# ai_firefly_prog.net
KiCad netlist of a schematic drawn in EAGLE
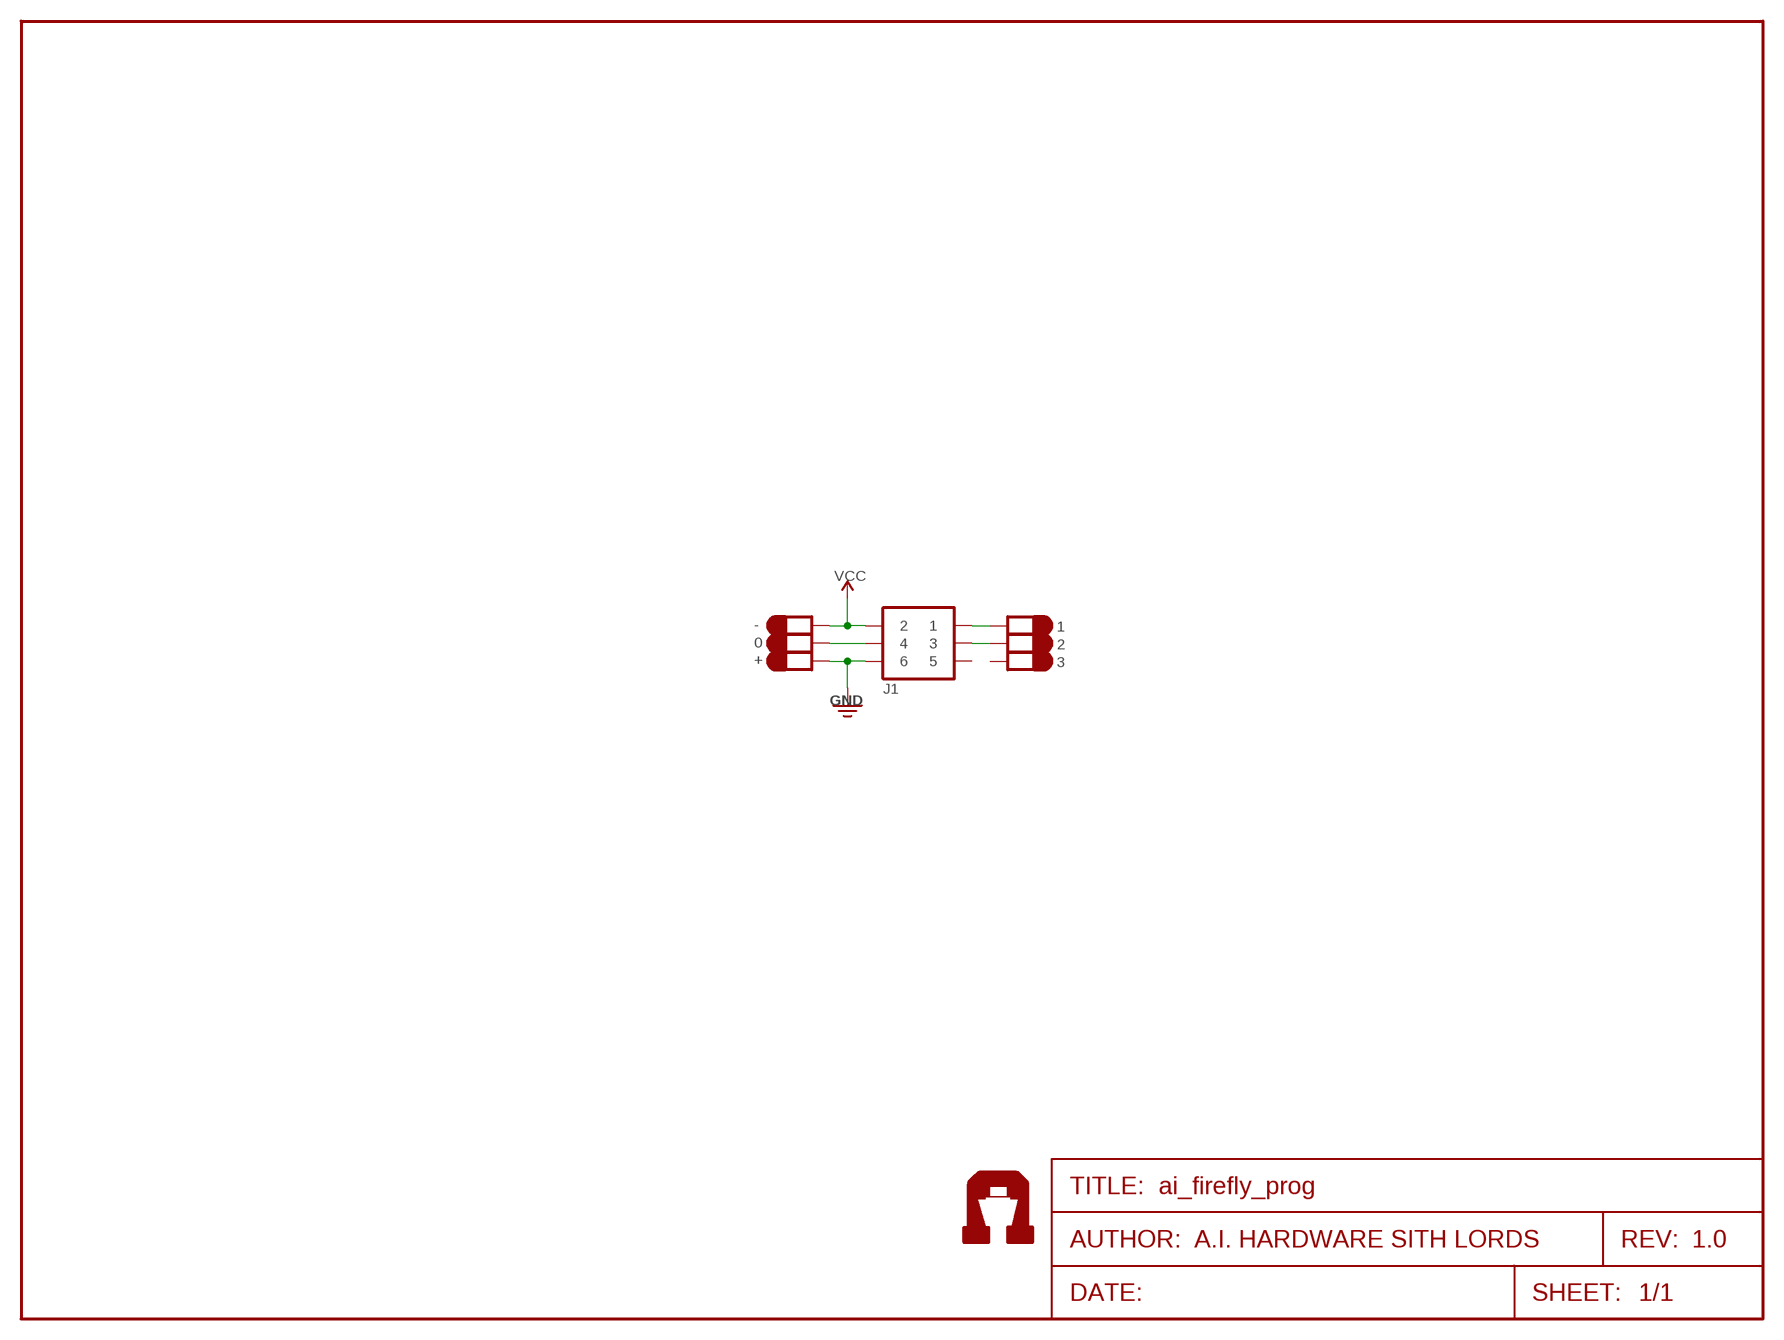
[diagram p0: schematic, sheet 1]

(export (version "E")
  (design (tool "Eeschema 10.0.6"))
  (components
    (comp (ref "+")
      (value "1X01-PETAL")
      (footprint "eagle-import:1X01-PETAL")
      (libsource (lib "eagle-import") (part "1X01-PETAL"))
    )
    (comp (ref "-")
      (value "1X01-PETAL")
      (footprint "eagle-import:1X01-PETAL")
      (libsource (lib "eagle-import") (part "1X01-PETAL"))
    )
    (comp (ref "0")
      (value "1X01-PETAL")
      (footprint "eagle-import:1X01-PETAL")
      (libsource (lib "eagle-import") (part "1X01-PETAL"))
    )
    (comp (ref "1")
      (value "1X01-PETAL")
      (footprint "eagle-import:1X01-PETAL")
      (libsource (lib "eagle-import") (part "1X01-PETAL"))
    )
    (comp (ref "2")
      (value "1X01-PETAL")
      (footprint "eagle-import:1X01-PETAL")
      (libsource (lib "eagle-import") (part "1X01-PETAL"))
    )
    (comp (ref "3")
      (value "1X01-PETAL")
      (footprint "eagle-import:1X01-PETAL")
      (libsource (lib "eagle-import") (part "1X01-PETAL"))
    )
    (comp (ref "J1")
      (value "2X03")
      (footprint "eagle-import:2X03")
      (libsource (lib "eagle-import") (part "2X03"))
    )
    (comp (ref "U$9")
      (value "AI-LOGOXS")
      (footprint "eagle-import:AI-LOGO-XS")
      (libsource (lib "eagle-import") (part "AI-LOGOXS"))
    )
  )
  (nets
    (net (code "1") (name "GND") (class "Default")
      (node (ref "+") (pin "1") (pinfunction "1_1") (pintype "bidirectional"))
      (node (ref "J1") (pin "6") (pinfunction "6_6") (pintype "bidirectional"))
    )
    (net (code "2") (name "Net-(0-Pad1)") (class "Default")
      (node (ref "0") (pin "1") (pinfunction "1_1") (pintype "bidirectional"))
      (node (ref "J1") (pin "4") (pinfunction "4_4") (pintype "bidirectional"))
    )
    (net (code "3") (name "Net-(1-Pad1)") (class "Default")
      (node (ref "1") (pin "1") (pinfunction "1_1") (pintype "bidirectional"))
      (node (ref "J1") (pin "1") (pinfunction "1_1") (pintype "bidirectional"))
    )
    (net (code "4") (name "Net-(2-Pad1)") (class "Default")
      (node (ref "2") (pin "1") (pinfunction "1_1") (pintype "bidirectional"))
      (node (ref "J1") (pin "3") (pinfunction "3_3") (pintype "bidirectional"))
    )
    (net (code "5") (name "VCC") (class "Default")
      (node (ref "-") (pin "1") (pinfunction "1_1") (pintype "bidirectional"))
      (node (ref "J1") (pin "2") (pinfunction "2_2") (pintype "bidirectional"))
    )
    (net (code "6") (name "unconnected-(3-Pad1)") (class "Default")
      (node (ref "3") (pin "1") (pinfunction "1_1") (pintype "bidirectional"))
    )
    (net (code "7") (name "unconnected-(J1-Pad5)") (class "Default")
      (node (ref "J1") (pin "5") (pinfunction "5_5") (pintype "bidirectional"))
    )
  )
)
